# Temperature_Control_LAB.net
KiCad netlist of a schematic drawn in EAGLE
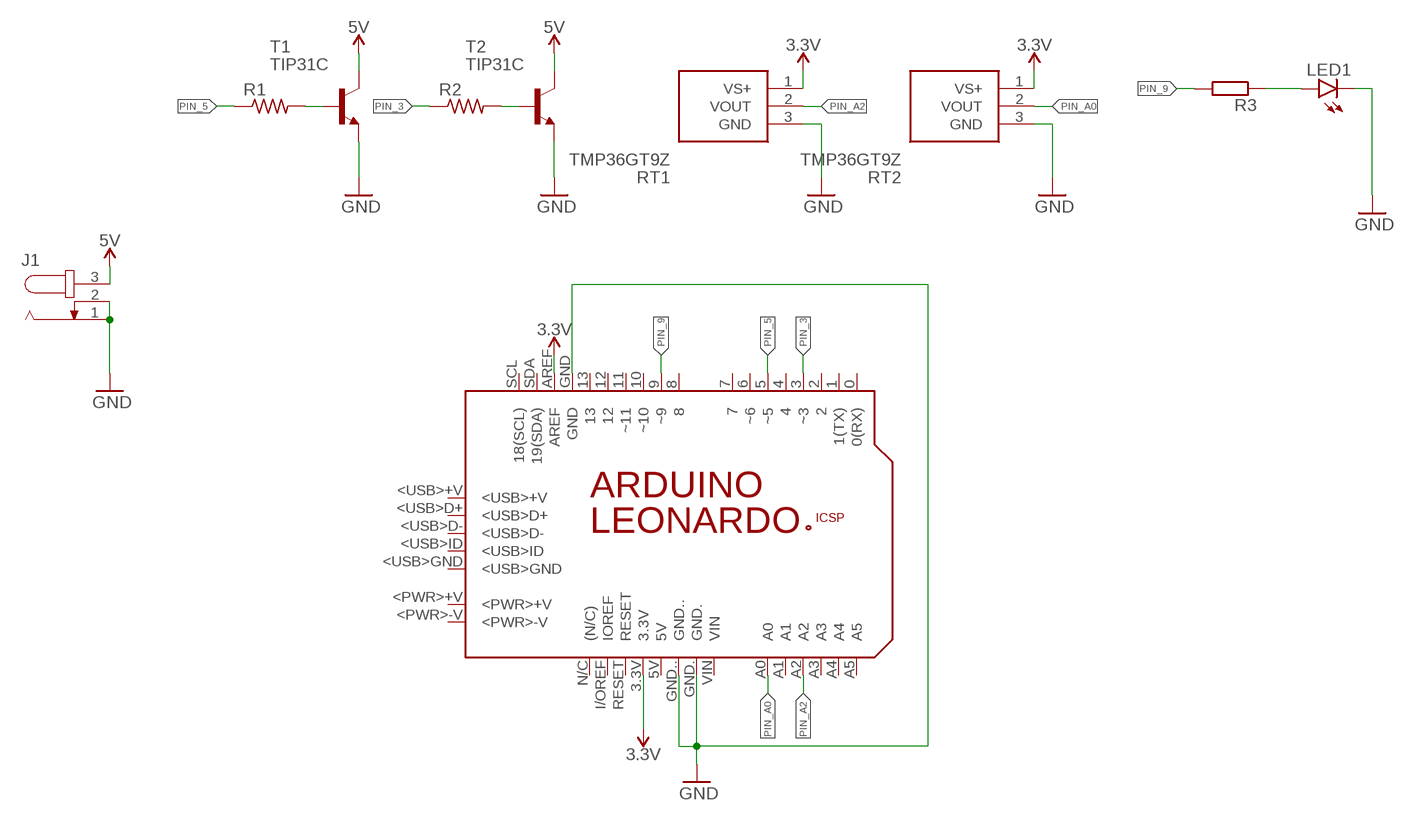
[diagram p0: schematic, sheet 1]

(export (version "E")
  (design (tool "Eeschema 10.0.6"))
  (components
    (comp (ref "J1")
      (value "JACK-PLUG0")
      (footprint "eagle-import:SPC4077")
      (libsource (lib "eagle-import") (part "JACK-PLUG0"))
    )
    (comp (ref "LED1")
      (value "LED5MM")
      (footprint "eagle-import:LED5MM")
      (libsource (lib "eagle-import") (part "LED5MM"))
    )
    (comp (ref "PCB1")
      (value "ARDUINO_LEONARDO")
      (footprint "eagle-import:ARDUINO_LEONARDO")
      (libsource (lib "eagle-import") (part "ARDUINO_LEONARDO"))
    )
    (comp (ref "R1")
      (value "R-US_M0805")
      (footprint "eagle-import:M0805")
      (libsource (lib "eagle-import") (part "R-US_M0805"))
    )
    (comp (ref "R2")
      (value "R-US_M0805")
      (footprint "eagle-import:M0805")
      (libsource (lib "eagle-import") (part "R-US_M0805"))
    )
    (comp (ref "R3")
      (value "R-EU_R0805")
      (footprint "eagle-import:R0805")
      (libsource (lib "eagle-import") (part "R-EU_R0805"))
    )
    (comp (ref "RT1")
      (value "TMP36GT9Z")
      (footprint "eagle-import:TO-92")
      (fields (field (name "MOUSER_PART_NUMBER") "584-TMP36GT9Z"))
      (libsource (lib "eagle-import") (part "TMP36GT9Z"))
    )
    (comp (ref "RT2")
      (value "TMP36GT9Z")
      (footprint "eagle-import:TO-92")
      (fields (field (name "MOUSER_PART_NUMBER") "584-TMP36GT9Z"))
      (libsource (lib "eagle-import") (part "TMP36GT9Z"))
    )
    (comp (ref "T1")
      (value "TIP31C")
      (footprint "eagle-import:TO220")
      (fields (field (name "MF") "STMicroelectronics"))
      (libsource (lib "eagle-import") (part "TIP31C"))
    )
    (comp (ref "T2")
      (value "TIP31C")
      (footprint "eagle-import:TO220")
      (fields (field (name "MF") "STMicroelectronics"))
      (libsource (lib "eagle-import") (part "TIP31C"))
    )
  )
  (nets
    (net (code "1") (name "3.3V") (class "Default")
      (node (ref "PCB1") (pin "3.3V") (pinfunction "3.3V_3.3V") (pintype "bidirectional"))
      (node (ref "PCB1") (pin "AREF") (pinfunction "AREF_AREF") (pintype "bidirectional"))
      (node (ref "RT1") (pin "1") (pinfunction "VS+_1") (pintype "power_in"))
      (node (ref "RT2") (pin "1") (pinfunction "VS+_1") (pintype "power_in"))
    )
    (net (code "2") (name "5V") (class "Default")
      (node (ref "J1") (pin "3") (pinfunction "3_3") (pintype "passive"))
      (node (ref "T1") (pin "2") (pinfunction "C_2") (pintype "passive"))
      (node (ref "T2") (pin "2") (pinfunction "C_2") (pintype "passive"))
    )
    (net (code "3") (name "GND") (class "Default")
      (node (ref "J1") (pin "1") (pinfunction "1_1") (pintype "passive"))
      (node (ref "J1") (pin "2") (pinfunction "2_2") (pintype "passive"))
      (node (ref "LED1") (pin "K") (pinfunction "C_K") (pintype "passive"))
      (node (ref "PCB1") (pin "GND") (pinfunction "GND_GND") (pintype "bidirectional"))
      (node (ref "PCB1") (pin "GND.") (pinfunction "GND._GND.") (pintype "bidirectional"))
      (node (ref "PCB1") (pin "GND..") (pinfunction "GND.._GND..") (pintype "bidirectional"))
      (node (ref "RT1") (pin "3") (pinfunction "GND_3") (pintype "power_in"))
      (node (ref "RT2") (pin "3") (pinfunction "GND_3") (pintype "power_in"))
      (node (ref "T1") (pin "3") (pinfunction "E_3") (pintype "passive"))
      (node (ref "T2") (pin "3") (pinfunction "E_3") (pintype "passive"))
    )
    (net (code "4") (name "Net-(LED1-PadA)") (class "Default")
      (node (ref "LED1") (pin "A") (pinfunction "A_A") (pintype "passive"))
      (node (ref "R3") (pin "1") (pinfunction "1_1") (pintype "passive"))
    )
    (net (code "5") (name "Net-(T1-B)") (class "Default")
      (node (ref "R1") (pin "2") (pinfunction "2_2") (pintype "passive"))
      (node (ref "T1") (pin "1") (pinfunction "B_1") (pintype "passive"))
    )
    (net (code "6") (name "Net-(T2-B)") (class "Default")
      (node (ref "R2") (pin "2") (pinfunction "2_2") (pintype "passive"))
      (node (ref "T2") (pin "1") (pinfunction "B_1") (pintype "passive"))
    )
    (net (code "7") (name "PIN_3") (class "Default")
      (node (ref "PCB1") (pin "3") (pinfunction "~{3}_3") (pintype "bidirectional"))
      (node (ref "R2") (pin "1") (pinfunction "1_1") (pintype "passive"))
    )
    (net (code "8") (name "PIN_5") (class "Default")
      (node (ref "PCB1") (pin "5") (pinfunction "~{5}_5") (pintype "bidirectional"))
      (node (ref "R1") (pin "1") (pinfunction "1_1") (pintype "passive"))
    )
    (net (code "9") (name "PIN_9") (class "Default")
      (node (ref "PCB1") (pin "9") (pinfunction "~{9}_9") (pintype "bidirectional"))
      (node (ref "R3") (pin "2") (pinfunction "2_2") (pintype "passive"))
    )
    (net (code "10") (name "PIN_A0") (class "Default")
      (node (ref "PCB1") (pin "A0") (pinfunction "A0_A0") (pintype "bidirectional"))
      (node (ref "RT2") (pin "2") (pinfunction "VOUT_2") (pintype "output"))
    )
    (net (code "11") (name "PIN_A2") (class "Default")
      (node (ref "PCB1") (pin "A2") (pinfunction "A2_A2") (pintype "bidirectional"))
      (node (ref "RT1") (pin "2") (pinfunction "VOUT_2") (pintype "output"))
    )
    (net (code "12") (name "unconnected-(PCB1-(N{slash}C)-PadN{slash}C)") (class "Default")
      (node (ref "PCB1") (pin "N/C") (pinfunction "(N/C)_N/C") (pintype "bidirectional"))
    )
    (net (code "13") (name "unconnected-(PCB1-0(RX)-Pad0)") (class "Default")
      (node (ref "PCB1") (pin "0") (pinfunction "0(RX)_0") (pintype "bidirectional"))
    )
    (net (code "14") (name "unconnected-(PCB1-1(TX)-Pad1)") (class "Default")
      (node (ref "PCB1") (pin "1") (pinfunction "1(TX)_1") (pintype "bidirectional"))
    )
    (net (code "15") (name "unconnected-(PCB1-18(SCL)-PadSCL)") (class "Default")
      (node (ref "PCB1") (pin "SCL") (pinfunction "18(SCL)_SCL") (pintype "bidirectional"))
    )
    (net (code "16") (name "unconnected-(PCB1-19(SDA)-PadSDA)") (class "Default")
      (node (ref "PCB1") (pin "SDA") (pinfunction "19(SDA)_SDA") (pintype "bidirectional"))
    )
    (net (code "17") (name "unconnected-(PCB1-IOREF-PadI{slash}OREF)") (class "Default")
      (node (ref "PCB1") (pin "I/OREF") (pinfunction "IOREF_I/OREF") (pintype "bidirectional"))
    )
    (net (code "18") (name "unconnected-(PCB1-Pad+5V)") (class "Default")
      (node (ref "PCB1") (pin "+5V") (pinfunction "+5V_+5V") (pintype "bidirectional"))
    )
    (net (code "19") (name "unconnected-(PCB1-Pad2)") (class "Default")
      (node (ref "PCB1") (pin "2") (pinfunction "2_2") (pintype "bidirectional"))
    )
    (net (code "20") (name "unconnected-(PCB1-Pad4)") (class "Default")
      (node (ref "PCB1") (pin "4") (pinfunction "4_4") (pintype "bidirectional"))
    )
    (net (code "21") (name "unconnected-(PCB1-Pad5V)") (class "Default")
      (node (ref "PCB1") (pin "5V") (pinfunction "5V_5V") (pintype "bidirectional"))
    )
    (net (code "22") (name "unconnected-(PCB1-Pad7)") (class "Default")
      (node (ref "PCB1") (pin "7") (pinfunction "7_7") (pintype "bidirectional"))
    )
    (net (code "23") (name "unconnected-(PCB1-Pad8)") (class "Default")
      (node (ref "PCB1") (pin "8") (pinfunction "8_8") (pintype "bidirectional"))
    )
    (net (code "24") (name "unconnected-(PCB1-Pad12)") (class "Default")
      (node (ref "PCB1") (pin "12") (pinfunction "12_12") (pintype "bidirectional"))
    )
    (net (code "25") (name "unconnected-(PCB1-Pad13)") (class "Default")
      (node (ref "PCB1") (pin "13") (pinfunction "13_13") (pintype "bidirectional"))
    )
    (net (code "26") (name "unconnected-(PCB1-Pad<PWR>+V)") (class "Default")
      (node (ref "PCB1") (pin "<PWR>+V") (pinfunction "<PWR>+V_<PWR>+V") (pintype "bidirectional"))
    )
    (net (code "27") (name "unconnected-(PCB1-Pad<PWR>-V)") (class "Default")
      (node (ref "PCB1") (pin "<PWR>-V") (pinfunction "<PWR>-V_<PWR>-V") (pintype "bidirectional"))
    )
    (net (code "28") (name "unconnected-(PCB1-Pad<USB>+V)") (class "Default")
      (node (ref "PCB1") (pin "<USB>+V") (pinfunction "<USB>+V_<USB>+V") (pintype "bidirectional"))
    )
    (net (code "29") (name "unconnected-(PCB1-Pad<USB>D+)") (class "Default")
      (node (ref "PCB1") (pin "<USB>D+") (pinfunction "<USB>D+_<USB>D+") (pintype "bidirectional"))
    )
    (net (code "30") (name "unconnected-(PCB1-Pad<USB>D-)") (class "Default")
      (node (ref "PCB1") (pin "<USB>D-") (pinfunction "<USB>D-_<USB>D-") (pintype "bidirectional"))
    )
    (net (code "31") (name "unconnected-(PCB1-Pad<USB>GND)") (class "Default")
      (node (ref "PCB1") (pin "<USB>GND") (pinfunction "<USB>GND_<USB>GND") (pintype "bidirectional"))
    )
    (net (code "32") (name "unconnected-(PCB1-Pad<USB>ID)") (class "Default")
      (node (ref "PCB1") (pin "<USB>ID") (pinfunction "<USB>ID_<USB>ID") (pintype "bidirectional"))
    )
    (net (code "33") (name "unconnected-(PCB1-PadA1)") (class "Default")
      (node (ref "PCB1") (pin "A1") (pinfunction "A1_A1") (pintype "bidirectional"))
    )
    (net (code "34") (name "unconnected-(PCB1-PadA3)") (class "Default")
      (node (ref "PCB1") (pin "A3") (pinfunction "A3_A3") (pintype "bidirectional"))
    )
    (net (code "35") (name "unconnected-(PCB1-PadA4)") (class "Default")
      (node (ref "PCB1") (pin "A4") (pinfunction "A4_A4") (pintype "bidirectional"))
    )
    (net (code "36") (name "unconnected-(PCB1-PadA5)") (class "Default")
      (node (ref "PCB1") (pin "A5") (pinfunction "A5_A5") (pintype "bidirectional"))
    )
    (net (code "37") (name "unconnected-(PCB1-PadGND_)") (class "Default")
      (node (ref "PCB1") (pin "GND_") (pinfunction "GND__GND_") (pintype "bidirectional"))
    )
    (net (code "38") (name "unconnected-(PCB1-PadMISO)") (class "Default")
      (node (ref "PCB1") (pin "MISO") (pinfunction "MISO_MISO") (pintype "bidirectional"))
    )
    (net (code "39") (name "unconnected-(PCB1-PadMOSI)") (class "Default")
      (node (ref "PCB1") (pin "MOSI") (pinfunction "MOSI_MOSI") (pintype "bidirectional"))
    )
    (net (code "40") (name "unconnected-(PCB1-PadRESET)") (class "Default")
      (node (ref "PCB1") (pin "RESET") (pinfunction "RESET_RESET") (pintype "bidirectional"))
    )
    (net (code "41") (name "unconnected-(PCB1-PadRESET.)") (class "Default")
      (node (ref "PCB1") (pin "RESET.") (pinfunction "RESET._RESET.") (pintype "bidirectional"))
    )
    (net (code "42") (name "unconnected-(PCB1-PadSCK)") (class "Default")
      (node (ref "PCB1") (pin "SCK") (pinfunction "SCK_SCK") (pintype "bidirectional"))
    )
    (net (code "43") (name "unconnected-(PCB1-PadVIN)") (class "Default")
      (node (ref "PCB1") (pin "VIN") (pinfunction "VIN_VIN") (pintype "bidirectional"))
    )
    (net (code "44") (name "unconnected-(PCB1-~{6}-Pad6)") (class "Default")
      (node (ref "PCB1") (pin "6") (pinfunction "~{6}_6") (pintype "bidirectional"))
    )
    (net (code "45") (name "unconnected-(PCB1-~{10}-Pad10)") (class "Default")
      (node (ref "PCB1") (pin "10") (pinfunction "~{10}_10") (pintype "bidirectional"))
    )
    (net (code "46") (name "unconnected-(PCB1-~{11}-Pad11)") (class "Default")
      (node (ref "PCB1") (pin "11") (pinfunction "~{11}_11") (pintype "bidirectional"))
    )
  )
)
